# ESP8266_MainBoard.net
KiCad netlist of a schematic drawn in EAGLE
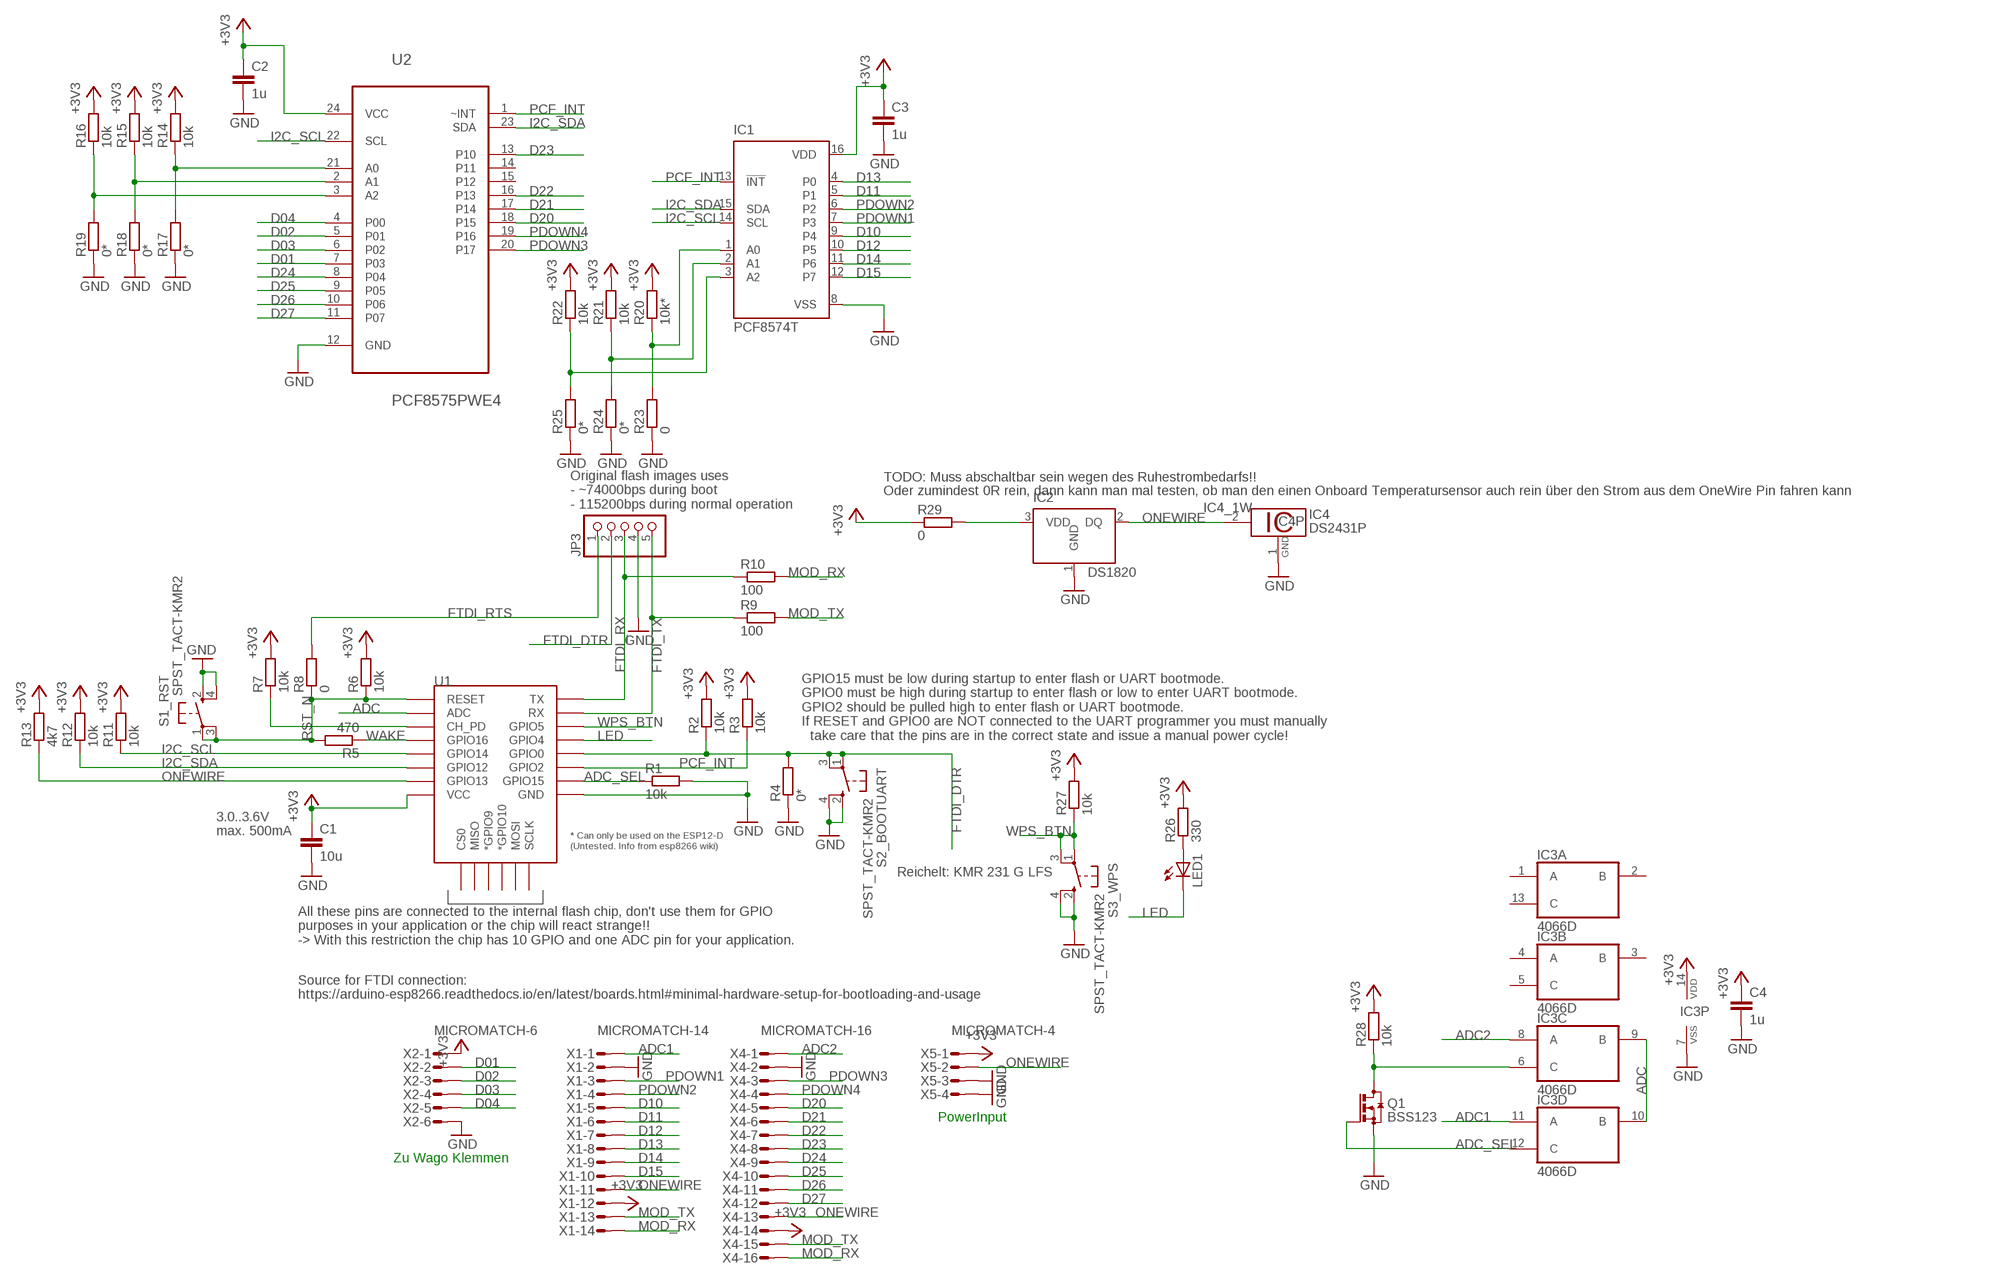
[diagram p0: schematic, sheet 1]

(export (version "E")
  (design (tool "Eeschema 10.0.6"))
  (components
    (comp (ref "C1")
      (value "10u")
      (footprint "eagle-import:C0805")
      (libsource (lib "eagle-import") (part "C-EUC0805"))
    )
    (comp (ref "C2")
      (value "1u")
      (footprint "eagle-import:C0402")
      (libsource (lib "eagle-import") (part "C-EUC0402"))
    )
    (comp (ref "C3")
      (value "1u")
      (footprint "eagle-import:C0402")
      (libsource (lib "eagle-import") (part "C-EUC0402"))
    )
    (comp (ref "C4")
      (value "1u")
      (footprint "eagle-import:C0402")
      (libsource (lib "eagle-import") (part "C-EUC0402"))
    )
    (comp (ref "IC1")
      (value "PCF8574T")
      (footprint "eagle-import:SO16W")
      (fields (field (name "MPN") "PCF8574T/3,512"))
      (libsource (lib "eagle-import") (part "PCF8574T"))
    )
    (comp (ref "IC2")
      (value "DS1820")
      (footprint "eagle-import:TO-92")
      (libsource (lib "eagle-import") (part "DS1820"))
    )
    (comp (ref "IC3")
      (value "4066D")
      (footprint "eagle-import:SO14")
      (libsource (lib "eagle-import") (part "4066D"))
    )
    (comp (ref "IC4")
      (value "DS2431P")
      (footprint "eagle-import:TSOC6")
      (libsource (lib "eagle-import") (part "DS2431P"))
    )
    (comp (ref "JP3")
      (value "PINHD-1X5")
      (footprint "eagle-import:1X05")
      (libsource (lib "eagle-import") (part "PINHD-1X5"))
    )
    (comp (ref "LED1")
      (value "LEDCHIP-LED0603")
      (footprint "eagle-import:CHIP-LED0603")
      (libsource (lib "eagle-import") (part "LEDCHIP-LED0603"))
    )
    (comp (ref "Q1")
      (value "BSS123")
      (footprint "eagle-import:SOT23")
      (libsource (lib "eagle-import") (part "BSS123"))
    )
    (comp (ref "R1")
      (value "10k")
      (footprint "eagle-import:R0402")
      (libsource (lib "eagle-import") (part "R-EU_R0402"))
    )
    (comp (ref "R2")
      (value "10k")
      (footprint "eagle-import:R0402")
      (libsource (lib "eagle-import") (part "R-EU_R0402"))
    )
    (comp (ref "R3")
      (value "10k")
      (footprint "eagle-import:R0402")
      (libsource (lib "eagle-import") (part "R-EU_R0402"))
    )
    (comp (ref "R4")
      (value "0*")
      (footprint "eagle-import:R0402")
      (libsource (lib "eagle-import") (part "R-EU_R0402"))
    )
    (comp (ref "R5")
      (value "470")
      (footprint "eagle-import:R0402")
      (libsource (lib "eagle-import") (part "R-EU_R0402"))
    )
    (comp (ref "R6")
      (value "10k")
      (footprint "eagle-import:R0402")
      (libsource (lib "eagle-import") (part "R-EU_R0402"))
    )
    (comp (ref "R7")
      (value "10k")
      (footprint "eagle-import:R0402")
      (libsource (lib "eagle-import") (part "R-EU_R0402"))
    )
    (comp (ref "R8")
      (value "0")
      (footprint "eagle-import:R0402")
      (libsource (lib "eagle-import") (part "R-EU_R0402"))
    )
    (comp (ref "R9")
      (value "100")
      (footprint "eagle-import:R0402")
      (libsource (lib "eagle-import") (part "R-EU_R0402"))
    )
    (comp (ref "R10")
      (value "100")
      (footprint "eagle-import:R0402")
      (libsource (lib "eagle-import") (part "R-EU_R0402"))
    )
    (comp (ref "R11")
      (value "10k")
      (footprint "eagle-import:R0402")
      (libsource (lib "eagle-import") (part "R-EU_R0402"))
    )
    (comp (ref "R12")
      (value "10k")
      (footprint "eagle-import:R0402")
      (libsource (lib "eagle-import") (part "R-EU_R0402"))
    )
    (comp (ref "R13")
      (value "4k7")
      (footprint "eagle-import:R0402")
      (libsource (lib "eagle-import") (part "R-EU_R0402"))
    )
    (comp (ref "R14")
      (value "10k")
      (footprint "eagle-import:R0402")
      (libsource (lib "eagle-import") (part "R-EU_R0402"))
    )
    (comp (ref "R15")
      (value "10k")
      (footprint "eagle-import:R0402")
      (libsource (lib "eagle-import") (part "R-EU_R0402"))
    )
    (comp (ref "R16")
      (value "10k")
      (footprint "eagle-import:R0402")
      (libsource (lib "eagle-import") (part "R-EU_R0402"))
    )
    (comp (ref "R17")
      (value "0*")
      (footprint "eagle-import:R0402")
      (libsource (lib "eagle-import") (part "R-EU_R0402"))
    )
    (comp (ref "R18")
      (value "0*")
      (footprint "eagle-import:R0402")
      (libsource (lib "eagle-import") (part "R-EU_R0402"))
    )
    (comp (ref "R19")
      (value "0*")
      (footprint "eagle-import:R0402")
      (libsource (lib "eagle-import") (part "R-EU_R0402"))
    )
    (comp (ref "R20")
      (value "10k*")
      (footprint "eagle-import:R0402")
      (libsource (lib "eagle-import") (part "R-EU_R0402"))
    )
    (comp (ref "R21")
      (value "10k")
      (footprint "eagle-import:R0402")
      (libsource (lib "eagle-import") (part "R-EU_R0402"))
    )
    (comp (ref "R22")
      (value "10k")
      (footprint "eagle-import:R0402")
      (libsource (lib "eagle-import") (part "R-EU_R0402"))
    )
    (comp (ref "R23")
      (value "0")
      (footprint "eagle-import:R0402")
      (libsource (lib "eagle-import") (part "R-EU_R0402"))
    )
    (comp (ref "R24")
      (value "0*")
      (footprint "eagle-import:R0402")
      (libsource (lib "eagle-import") (part "R-EU_R0402"))
    )
    (comp (ref "R25")
      (value "0*")
      (footprint "eagle-import:R0402")
      (libsource (lib "eagle-import") (part "R-EU_R0402"))
    )
    (comp (ref "R26")
      (value "330")
      (footprint "eagle-import:R0402")
      (libsource (lib "eagle-import") (part "R-EU_R0402"))
    )
    (comp (ref "R27")
      (value "10k")
      (footprint "eagle-import:R0402")
      (libsource (lib "eagle-import") (part "R-EU_R0402"))
    )
    (comp (ref "R28")
      (value "10k")
      (footprint "eagle-import:R0402")
      (libsource (lib "eagle-import") (part "R-EU_R0402"))
    )
    (comp (ref "R29")
      (value "0")
      (footprint "eagle-import:R0402")
      (libsource (lib "eagle-import") (part "R-EU_R0402"))
    )
    (comp (ref "S1_RST")
      (value "SPST_TACT-KMR2")
      (footprint "eagle-import:KMR2")
      (libsource (lib "eagle-import") (part "SPST_TACT-KMR2"))
    )
    (comp (ref "S2_BOOTUART")
      (value "SPST_TACT-KMR2")
      (footprint "eagle-import:KMR2")
      (libsource (lib "eagle-import") (part "SPST_TACT-KMR2"))
    )
    (comp (ref "S3_WPS")
      (value "SPST_TACT-KMR2")
      (footprint "eagle-import:KMR2")
      (libsource (lib "eagle-import") (part "SPST_TACT-KMR2"))
    )
    (comp (ref "U1")
      (value "ESP12ESMD")
      (footprint "eagle-import:ESP12E-SMD")
      (libsource (lib "eagle-import") (part "ESP12ESMD"))
    )
    (comp (ref "U2")
      (value "PCF8575PWE4")
      (footprint "eagle-import:SOP65P640X120-24N")
      (fields (field (name "MF") "Texas Instruments"))
      (libsource (lib "eagle-import") (part "PCF8575PWE4"))
    )
    (comp (ref "X1")
      (value "MICROMATCH-14")
      (footprint "eagle-import:MICROMATCH-14")
      (fields (field (name "MF") "FARNELL") (field (name "MPN") "8-215464-4"))
      (libsource (lib "eagle-import") (part "MICROMATCH-14"))
    )
    (comp (ref "X2")
      (value "MICROMATCH-6")
      (footprint "eagle-import:MICROMATCH-6")
      (fields (field (name "MPN") "7-215464-6"))
      (libsource (lib "eagle-import") (part "MICROMATCH-6"))
    )
    (comp (ref "X4")
      (value "MICROMATCH-16")
      (footprint "eagle-import:MICROMATCH-16")
      (fields (field (name "MF") "FARNELL") (field (name "MPN") "8-215464-6"))
      (libsource (lib "eagle-import") (part "MICROMATCH-16"))
    )
    (comp (ref "X5")
      (value "MICROMATCH-4")
      (footprint "eagle-import:MICROMATCH-4")
      (fields (field (name "MPN") "7-215464-4"))
      (libsource (lib "eagle-import") (part "MICROMATCH-4"))
    )
  )
  (nets
    (net (code "1") (name "+3V3") (class "Default")
      (node (ref "C1") (pin "1") (pinfunction "1_1") (pintype "passive"))
      (node (ref "C2") (pin "1") (pinfunction "1_1") (pintype "passive"))
      (node (ref "C3") (pin "1") (pinfunction "1_1") (pintype "passive"))
      (node (ref "C4") (pin "1") (pinfunction "1_1") (pintype "passive"))
      (node (ref "IC1") (pin "16") (pinfunction "VDD_16") (pintype "power_in"))
      (node (ref "IC3") (pin "14") (pinfunction "VDD_14") (pintype "power_in"))
      (node (ref "R11") (pin "2") (pinfunction "2_2") (pintype "passive"))
      (node (ref "R12") (pin "2") (pinfunction "2_2") (pintype "passive"))
      (node (ref "R13") (pin "2") (pinfunction "2_2") (pintype "passive"))
      (node (ref "R14") (pin "2") (pinfunction "2_2") (pintype "passive"))
      (node (ref "R15") (pin "2") (pinfunction "2_2") (pintype "passive"))
      (node (ref "R16") (pin "2") (pinfunction "2_2") (pintype "passive"))
      (node (ref "R2") (pin "2") (pinfunction "2_2") (pintype "passive"))
      (node (ref "R20") (pin "2") (pinfunction "2_2") (pintype "passive"))
      (node (ref "R21") (pin "2") (pinfunction "2_2") (pintype "passive"))
      (node (ref "R22") (pin "2") (pinfunction "2_2") (pintype "passive"))
      (node (ref "R26") (pin "2") (pinfunction "2_2") (pintype "passive"))
      (node (ref "R27") (pin "2") (pinfunction "2_2") (pintype "passive"))
      (node (ref "R28") (pin "2") (pinfunction "2_2") (pintype "passive"))
      (node (ref "R29") (pin "1") (pinfunction "1_1") (pintype "passive"))
      (node (ref "R3") (pin "2") (pinfunction "2_2") (pintype "passive"))
      (node (ref "R6") (pin "2") (pinfunction "2_2") (pintype "passive"))
      (node (ref "R7") (pin "2") (pinfunction "2_2") (pintype "passive"))
      (node (ref "U1") (pin "VCC") (pinfunction "VCC_VCC") (pintype "bidirectional"))
      (node (ref "U2") (pin "24") (pinfunction "VCC_24") (pintype "power_in"))
      (node (ref "X1") (pin "12") (pinfunction "S_12") (pintype "passive"))
      (node (ref "X2") (pin "1") (pinfunction "S_1") (pintype "passive"))
      (node (ref "X4") (pin "14") (pinfunction "S_14") (pintype "passive"))
      (node (ref "X5") (pin "1") (pinfunction "S_1") (pintype "passive"))
    )
    (net (code "2") (name "/ADC") (class "Default")
      (node (ref "IC3") (pin "10") (pinfunction "B_10") (pintype "tri_state"))
      (node (ref "IC3") (pin "9") (pinfunction "B_9") (pintype "tri_state"))
      (node (ref "U1") (pin "ADC") (pinfunction "ADC_ADC") (pintype "bidirectional"))
    )
    (net (code "3") (name "/ADC1") (class "Default")
      (node (ref "IC3") (pin "11") (pinfunction "A_11") (pintype "tri_state"))
      (node (ref "X1") (pin "1") (pinfunction "S_1") (pintype "passive"))
    )
    (net (code "4") (name "/ADC2") (class "Default")
      (node (ref "IC3") (pin "8") (pinfunction "A_8") (pintype "tri_state"))
      (node (ref "X4") (pin "1") (pinfunction "S_1") (pintype "passive"))
    )
    (net (code "5") (name "/ADC_SEL") (class "Default")
      (node (ref "IC3") (pin "12") (pinfunction "C_12") (pintype "input"))
      (node (ref "Q1") (pin "1") (pinfunction "G_1") (pintype "passive"))
      (node (ref "R1") (pin "1") (pinfunction "1_1") (pintype "passive"))
      (node (ref "U1") (pin "GPIO15") (pinfunction "GPIO15_GPIO15") (pintype "bidirectional"))
    )
    (net (code "6") (name "/D01") (class "Default")
      (node (ref "U2") (pin "7") (pinfunction "P03_7") (pintype "bidirectional"))
      (node (ref "X2") (pin "2") (pinfunction "S_2") (pintype "passive"))
    )
    (net (code "7") (name "/D02") (class "Default")
      (node (ref "U2") (pin "5") (pinfunction "P01_5") (pintype "bidirectional"))
      (node (ref "X2") (pin "3") (pinfunction "S_3") (pintype "passive"))
    )
    (net (code "8") (name "/D03") (class "Default")
      (node (ref "U2") (pin "6") (pinfunction "P02_6") (pintype "bidirectional"))
      (node (ref "X2") (pin "4") (pinfunction "S_4") (pintype "passive"))
    )
    (net (code "9") (name "/D04") (class "Default")
      (node (ref "U2") (pin "4") (pinfunction "P00_4") (pintype "bidirectional"))
      (node (ref "X2") (pin "5") (pinfunction "S_5") (pintype "passive"))
    )
    (net (code "10") (name "/D10") (class "Default")
      (node (ref "IC1") (pin "9") (pinfunction "P4_9") (pintype "bidirectional"))
      (node (ref "X1") (pin "5") (pinfunction "S_5") (pintype "passive"))
    )
    (net (code "11") (name "/D11") (class "Default")
      (node (ref "IC1") (pin "5") (pinfunction "P1_5") (pintype "bidirectional"))
      (node (ref "X1") (pin "6") (pinfunction "S_6") (pintype "passive"))
    )
    (net (code "12") (name "/D12") (class "Default")
      (node (ref "IC1") (pin "10") (pinfunction "P5_10") (pintype "bidirectional"))
      (node (ref "X1") (pin "7") (pinfunction "S_7") (pintype "passive"))
    )
    (net (code "13") (name "/D13") (class "Default")
      (node (ref "IC1") (pin "4") (pinfunction "P0_4") (pintype "bidirectional"))
      (node (ref "X1") (pin "8") (pinfunction "S_8") (pintype "passive"))
    )
    (net (code "14") (name "/D14") (class "Default")
      (node (ref "IC1") (pin "11") (pinfunction "P6_11") (pintype "bidirectional"))
      (node (ref "X1") (pin "9") (pinfunction "S_9") (pintype "passive"))
    )
    (net (code "15") (name "/D15") (class "Default")
      (node (ref "IC1") (pin "12") (pinfunction "P7_12") (pintype "bidirectional"))
      (node (ref "X1") (pin "10") (pinfunction "S_10") (pintype "passive"))
    )
    (net (code "16") (name "/D20") (class "Default")
      (node (ref "U2") (pin "18") (pinfunction "P15_18") (pintype "bidirectional"))
      (node (ref "X4") (pin "5") (pinfunction "S_5") (pintype "passive"))
    )
    (net (code "17") (name "/D21") (class "Default")
      (node (ref "U2") (pin "17") (pinfunction "P14_17") (pintype "bidirectional"))
      (node (ref "X4") (pin "6") (pinfunction "S_6") (pintype "passive"))
    )
    (net (code "18") (name "/D22") (class "Default")
      (node (ref "U2") (pin "16") (pinfunction "P13_16") (pintype "bidirectional"))
      (node (ref "X4") (pin "7") (pinfunction "S_7") (pintype "passive"))
    )
    (net (code "19") (name "/D23") (class "Default")
      (node (ref "U2") (pin "13") (pinfunction "P10_13") (pintype "bidirectional"))
      (node (ref "X4") (pin "8") (pinfunction "S_8") (pintype "passive"))
    )
    (net (code "20") (name "/D24") (class "Default")
      (node (ref "U2") (pin "8") (pinfunction "P04_8") (pintype "bidirectional"))
      (node (ref "X4") (pin "9") (pinfunction "S_9") (pintype "passive"))
    )
    (net (code "21") (name "/D25") (class "Default")
      (node (ref "U2") (pin "9") (pinfunction "P05_9") (pintype "bidirectional"))
      (node (ref "X4") (pin "10") (pinfunction "S_10") (pintype "passive"))
    )
    (net (code "22") (name "/D26") (class "Default")
      (node (ref "U2") (pin "10") (pinfunction "P06_10") (pintype "bidirectional"))
      (node (ref "X4") (pin "11") (pinfunction "S_11") (pintype "passive"))
    )
    (net (code "23") (name "/D27") (class "Default")
      (node (ref "U2") (pin "11") (pinfunction "P07_11") (pintype "bidirectional"))
      (node (ref "X4") (pin "12") (pinfunction "S_12") (pintype "passive"))
    )
    (net (code "24") (name "/FTDI_DTR") (class "Default")
      (node (ref "JP3") (pin "2") (pinfunction "2_2") (pintype "passive"))
      (node (ref "R2") (pin "1") (pinfunction "1_1") (pintype "passive"))
      (node (ref "R4") (pin "2") (pinfunction "2_2") (pintype "passive"))
      (node (ref "S2_BOOTUART") (pin "1") (pinfunction "P_1") (pintype "passive"))
      (node (ref "S2_BOOTUART") (pin "3") (pinfunction "P1_3") (pintype "passive"))
      (node (ref "U1") (pin "GPIO0") (pinfunction "GPIO0_GPIO0") (pintype "bidirectional"))
    )
    (net (code "25") (name "/FTDI_RTS") (class "Default")
      (node (ref "JP3") (pin "1") (pinfunction "1_1") (pintype "passive"))
      (node (ref "R8") (pin "2") (pinfunction "2_2") (pintype "passive"))
    )
    (net (code "26") (name "/FTDI_RX") (class "Default")
      (node (ref "JP3") (pin "3") (pinfunction "3_3") (pintype "passive"))
      (node (ref "R10") (pin "1") (pinfunction "1_1") (pintype "passive"))
      (node (ref "U1") (pin "TXD0") (pinfunction "TX_TXD0") (pintype "bidirectional"))
    )
    (net (code "27") (name "/FTDI_TX") (class "Default")
      (node (ref "JP3") (pin "5") (pinfunction "5_5") (pintype "passive"))
      (node (ref "R9") (pin "1") (pinfunction "1_1") (pintype "passive"))
      (node (ref "U1") (pin "RXD0") (pinfunction "RX_RXD0") (pintype "bidirectional"))
    )
    (net (code "28") (name "/I2C_SCL") (class "Default")
      (node (ref "IC1") (pin "14") (pinfunction "SCL_14") (pintype "input"))
      (node (ref "R11") (pin "1") (pinfunction "1_1") (pintype "passive"))
      (node (ref "U1") (pin "GPIO14") (pinfunction "GPIO14_GPIO14") (pintype "bidirectional"))
      (node (ref "U2") (pin "22") (pinfunction "SCL_22") (pintype "input"))
    )
    (net (code "29") (name "/I2C_SDA") (class "Default")
      (node (ref "IC1") (pin "15") (pinfunction "SDA_15") (pintype "bidirectional"))
      (node (ref "R12") (pin "1") (pinfunction "1_1") (pintype "passive"))
      (node (ref "U1") (pin "GPIO12") (pinfunction "GPIO12_GPIO12") (pintype "bidirectional"))
      (node (ref "U2") (pin "23") (pinfunction "SDA_23") (pintype "bidirectional"))
    )
    (net (code "30") (name "/LED") (class "Default")
      (node (ref "LED1") (pin "C") (pinfunction "C_C") (pintype "passive"))
      (node (ref "U1") (pin "GPIO4") (pinfunction "GPIO4_GPIO4") (pintype "bidirectional"))
    )
    (net (code "31") (name "/MOD_RX") (class "Default")
      (node (ref "R10") (pin "2") (pinfunction "2_2") (pintype "passive"))
      (node (ref "X1") (pin "14") (pinfunction "S_14") (pintype "passive"))
      (node (ref "X4") (pin "16") (pinfunction "S_16") (pintype "passive"))
    )
    (net (code "32") (name "/MOD_TX") (class "Default")
      (node (ref "R9") (pin "2") (pinfunction "2_2") (pintype "passive"))
      (node (ref "X1") (pin "13") (pinfunction "S_13") (pintype "passive"))
      (node (ref "X4") (pin "15") (pinfunction "S_15") (pintype "passive"))
    )
    (net (code "33") (name "/ONEWIRE") (class "Default")
      (node (ref "IC2") (pin "2") (pinfunction "DQ_2") (pintype "output"))
      (node (ref "IC4") (pin "2") (pinfunction "1W_2") (pintype "power_in"))
      (node (ref "R13") (pin "1") (pinfunction "1_1") (pintype "passive"))
      (node (ref "U1") (pin "GPIO13") (pinfunction "GPIO13_GPIO13") (pintype "bidirectional"))
      (node (ref "X1") (pin "11") (pinfunction "S_11") (pintype "passive"))
      (node (ref "X4") (pin "13") (pinfunction "S_13") (pintype "passive"))
      (node (ref "X5") (pin "2") (pinfunction "S_2") (pintype "passive"))
    )
    (net (code "34") (name "/PCF_INT") (class "Default")
      (node (ref "IC1") (pin "13") (pinfunction "~{INT}_13") (pintype "output"))
      (node (ref "R3") (pin "1") (pinfunction "1_1") (pintype "passive"))
      (node (ref "U1") (pin "GPIO2") (pinfunction "GPIO2_GPIO2") (pintype "bidirectional"))
      (node (ref "U2") (pin "1") (pinfunction "~{INT}_1") (pintype "output"))
    )
    (net (code "35") (name "/PDOWN1") (class "Default")
      (node (ref "IC1") (pin "7") (pinfunction "P3_7") (pintype "bidirectional"))
      (node (ref "X1") (pin "3") (pinfunction "S_3") (pintype "passive"))
    )
    (net (code "36") (name "/PDOWN2") (class "Default")
      (node (ref "IC1") (pin "6") (pinfunction "P2_6") (pintype "bidirectional"))
      (node (ref "X1") (pin "4") (pinfunction "S_4") (pintype "passive"))
    )
    (net (code "37") (name "/PDOWN3") (class "Default")
      (node (ref "U2") (pin "20") (pinfunction "P17_20") (pintype "bidirectional"))
      (node (ref "X4") (pin "3") (pinfunction "S_3") (pintype "passive"))
    )
    (net (code "38") (name "/PDOWN4") (class "Default")
      (node (ref "U2") (pin "19") (pinfunction "P16_19") (pintype "bidirectional"))
      (node (ref "X4") (pin "4") (pinfunction "S_4") (pintype "passive"))
    )
    (net (code "39") (name "/RST_N") (class "Default")
      (node (ref "R5") (pin "2") (pinfunction "2_2") (pintype "passive"))
      (node (ref "R6") (pin "1") (pinfunction "1_1") (pintype "passive"))
      (node (ref "R8") (pin "1") (pinfunction "1_1") (pintype "passive"))
      (node (ref "S1_RST") (pin "1") (pinfunction "P_1") (pintype "passive"))
      (node (ref "S1_RST") (pin "3") (pinfunction "P1_3") (pintype "passive"))
      (node (ref "U1") (pin "RESET") (pinfunction "RESET_RESET") (pintype "bidirectional"))
    )
    (net (code "40") (name "/WAKE") (class "Default")
      (node (ref "R5") (pin "1") (pinfunction "1_1") (pintype "passive"))
      (node (ref "U1") (pin "GPIO16") (pinfunction "GPIO16_GPIO16") (pintype "bidirectional"))
    )
    (net (code "41") (name "/WPS_BTN") (class "Default")
      (node (ref "R27") (pin "1") (pinfunction "1_1") (pintype "passive"))
      (node (ref "S3_WPS") (pin "1") (pinfunction "P_1") (pintype "passive"))
      (node (ref "S3_WPS") (pin "3") (pinfunction "P1_3") (pintype "passive"))
      (node (ref "U1") (pin "GPIO5") (pinfunction "GPIO5_GPIO5") (pintype "bidirectional"))
    )
    (net (code "42") (name "GND") (class "Default")
      (node (ref "C1") (pin "2") (pinfunction "2_2") (pintype "passive"))
      (node (ref "C2") (pin "2") (pinfunction "2_2") (pintype "passive"))
      (node (ref "C3") (pin "2") (pinfunction "2_2") (pintype "passive"))
      (node (ref "C4") (pin "2") (pinfunction "2_2") (pintype "passive"))
      (node (ref "IC1") (pin "8") (pinfunction "VSS_8") (pintype "power_in"))
      (node (ref "IC2") (pin "1") (pinfunction "GND_1") (pintype "power_in"))
      (node (ref "IC3") (pin "7") (pinfunction "VSS_7") (pintype "power_in"))
      (node (ref "IC4") (pin "1") (pinfunction "GND_1") (pintype "power_in"))
      (node (ref "JP3") (pin "4") (pinfunction "4_4") (pintype "passive"))
      (node (ref "Q1") (pin "2") (pinfunction "S_2") (pintype "passive"))
      (node (ref "R1") (pin "2") (pinfunction "2_2") (pintype "passive"))
      (node (ref "R17") (pin "1") (pinfunction "1_1") (pintype "passive"))
      (node (ref "R18") (pin "1") (pinfunction "1_1") (pintype "passive"))
      (node (ref "R19") (pin "1") (pinfunction "1_1") (pintype "passive"))
      (node (ref "R23") (pin "1") (pinfunction "1_1") (pintype "passive"))
      (node (ref "R24") (pin "1") (pinfunction "1_1") (pintype "passive"))
      (node (ref "R25") (pin "1") (pinfunction "1_1") (pintype "passive"))
      (node (ref "R4") (pin "1") (pinfunction "1_1") (pintype "passive"))
      (node (ref "S1_RST") (pin "2") (pinfunction "S_2") (pintype "passive"))
      (node (ref "S1_RST") (pin "4") (pinfunction "S1_4") (pintype "passive"))
      (node (ref "S2_BOOTUART") (pin "2") (pinfunction "S_2") (pintype "passive"))
      (node (ref "S2_BOOTUART") (pin "4") (pinfunction "S1_4") (pintype "passive"))
      (node (ref "S3_WPS") (pin "2") (pinfunction "S_2") (pintype "passive"))
      (node (ref "S3_WPS") (pin "4") (pinfunction "S1_4") (pintype "passive"))
      (node (ref "U1") (pin "GND") (pinfunction "GND_GND") (pintype "bidirectional"))
      (node (ref "U2") (pin "12") (pinfunction "GND_12") (pintype "passive"))
      (node (ref "X1") (pin "2") (pinfunction "S_2") (pintype "passive"))
      (node (ref "X2") (pin "6") (pinfunction "S_6") (pintype "passive"))
      (node (ref "X4") (pin "2") (pinfunction "S_2") (pintype "passive"))
      (node (ref "X5") (pin "3") (pinfunction "S_3") (pintype "passive"))
      (node (ref "X5") (pin "4") (pinfunction "S_4") (pintype "passive"))
    )
    (net (code "43") (name "Net-(IC1-A0)") (class "Default")
      (node (ref "IC1") (pin "1") (pinfunction "A0_1") (pintype "input"))
      (node (ref "R20") (pin "1") (pinfunction "1_1") (pintype "passive"))
      (node (ref "R23") (pin "2") (pinfunction "2_2") (pintype "passive"))
    )
    (net (code "44") (name "Net-(IC1-A1)") (class "Default")
      (node (ref "IC1") (pin "2") (pinfunction "A1_2") (pintype "input"))
      (node (ref "R21") (pin "1") (pinfunction "1_1") (pintype "passive"))
      (node (ref "R24") (pin "2") (pinfunction "2_2") (pintype "passive"))
    )
    (net (code "45") (name "Net-(IC1-A2)") (class "Default")
      (node (ref "IC1") (pin "3") (pinfunction "A2_3") (pintype "input"))
      (node (ref "R22") (pin "1") (pinfunction "1_1") (pintype "passive"))
      (node (ref "R25") (pin "2") (pinfunction "2_2") (pintype "passive"))
    )
    (net (code "46") (name "Net-(IC2-VDD)") (class "Default")
      (node (ref "IC2") (pin "3") (pinfunction "VDD_3") (pintype "input"))
      (node (ref "R29") (pin "2") (pinfunction "2_2") (pintype "passive"))
    )
    (net (code "47") (name "Net-(IC3C-C)") (class "Default")
      (node (ref "IC3") (pin "6") (pinfunction "C_6") (pintype "input"))
      (node (ref "Q1") (pin "3") (pinfunction "D_3") (pintype "passive"))
      (node (ref "R28") (pin "1") (pinfunction "1_1") (pintype "passive"))
    )
    (net (code "48") (name "Net-(LED1-PadA)") (class "Default")
      (node (ref "LED1") (pin "A") (pinfunction "A_A") (pintype "passive"))
      (node (ref "R26") (pin "1") (pinfunction "1_1") (pintype "passive"))
    )
    (net (code "49") (name "Net-(R7-Pad1)") (class "Default")
      (node (ref "R7") (pin "1") (pinfunction "1_1") (pintype "passive"))
      (node (ref "U1") (pin "CH_PD") (pinfunction "CH_PD_CH_PD") (pintype "bidirectional"))
    )
    (net (code "50") (name "Net-(U2-A0)") (class "Default")
      (node (ref "R14") (pin "1") (pinfunction "1_1") (pintype "passive"))
      (node (ref "R17") (pin "2") (pinfunction "2_2") (pintype "passive"))
      (node (ref "U2") (pin "21") (pinfunction "A0_21") (pintype "input"))
    )
    (net (code "51") (name "Net-(U2-A1)") (class "Default")
      (node (ref "R15") (pin "1") (pinfunction "1_1") (pintype "passive"))
      (node (ref "R18") (pin "2") (pinfunction "2_2") (pintype "passive"))
      (node (ref "U2") (pin "2") (pinfunction "A1_2") (pintype "input"))
    )
    (net (code "52") (name "Net-(U2-A2)") (class "Default")
      (node (ref "R16") (pin "1") (pinfunction "1_1") (pintype "passive"))
      (node (ref "R19") (pin "2") (pinfunction "2_2") (pintype "passive"))
      (node (ref "U2") (pin "3") (pinfunction "A2_3") (pintype "input"))
    )
    (net (code "53") (name "unconnected-(IC3A-A-Pad1)") (class "Default")
      (node (ref "IC3") (pin "1") (pinfunction "A_1") (pintype "tri_state"))
    )
    (net (code "54") (name "unconnected-(IC3A-B-Pad2)") (class "Default")
      (node (ref "IC3") (pin "2") (pinfunction "B_2") (pintype "tri_state"))
    )
    (net (code "55") (name "unconnected-(IC3A-C-Pad13)") (class "Default")
      (node (ref "IC3") (pin "13") (pinfunction "C_13") (pintype "input"))
    )
    (net (code "56") (name "unconnected-(IC3B-A-Pad4)") (class "Default")
      (node (ref "IC3") (pin "4") (pinfunction "A_4") (pintype "tri_state"))
    )
    (net (code "57") (name "unconnected-(IC3B-B-Pad3)") (class "Default")
      (node (ref "IC3") (pin "3") (pinfunction "B_3") (pintype "tri_state"))
    )
    (net (code "58") (name "unconnected-(IC3B-C-Pad5)") (class "Default")
      (node (ref "IC3") (pin "5") (pinfunction "C_5") (pintype "input"))
    )
    (net (code "59") (name "unconnected-(U1-*GPIO9-PadGPIO9)") (class "Default")
      (node (ref "U1") (pin "GPIO9") (pinfunction "*GPIO9_GPIO9") (pintype "bidirectional"))
    )
    (net (code "60") (name "unconnected-(U1-*GPIO10-PadGPIO10)") (class "Default")
      (node (ref "U1") (pin "GPIO10") (pinfunction "*GPIO10_GPIO10") (pintype "bidirectional"))
    )
    (net (code "61") (name "unconnected-(U1-PadCS0)") (class "Default")
      (node (ref "U1") (pin "CS0") (pinfunction "CS0_CS0") (pintype "bidirectional"))
    )
    (net (code "62") (name "unconnected-(U1-PadMISO)") (class "Default")
      (node (ref "U1") (pin "MISO") (pinfunction "MISO_MISO") (pintype "bidirectional"))
    )
    (net (code "63") (name "unconnected-(U1-PadMOSI)") (class "Default")
      (node (ref "U1") (pin "MOSI") (pinfunction "MOSI_MOSI") (pintype "bidirectional"))
    )
    (net (code "64") (name "unconnected-(U1-PadSCLK)") (class "Default")
      (node (ref "U1") (pin "SCLK") (pinfunction "SCLK_SCLK") (pintype "bidirectional"))
    )
    (net (code "65") (name "unconnected-(U2-P11-Pad14)") (class "Default")
      (node (ref "U2") (pin "14") (pinfunction "P11_14") (pintype "bidirectional"))
    )
    (net (code "66") (name "unconnected-(U2-P12-Pad15)") (class "Default")
      (node (ref "U2") (pin "15") (pinfunction "P12_15") (pintype "bidirectional"))
    )
  )
)
